# MKR1000.net
KiCad netlist of a schematic drawn in EAGLE
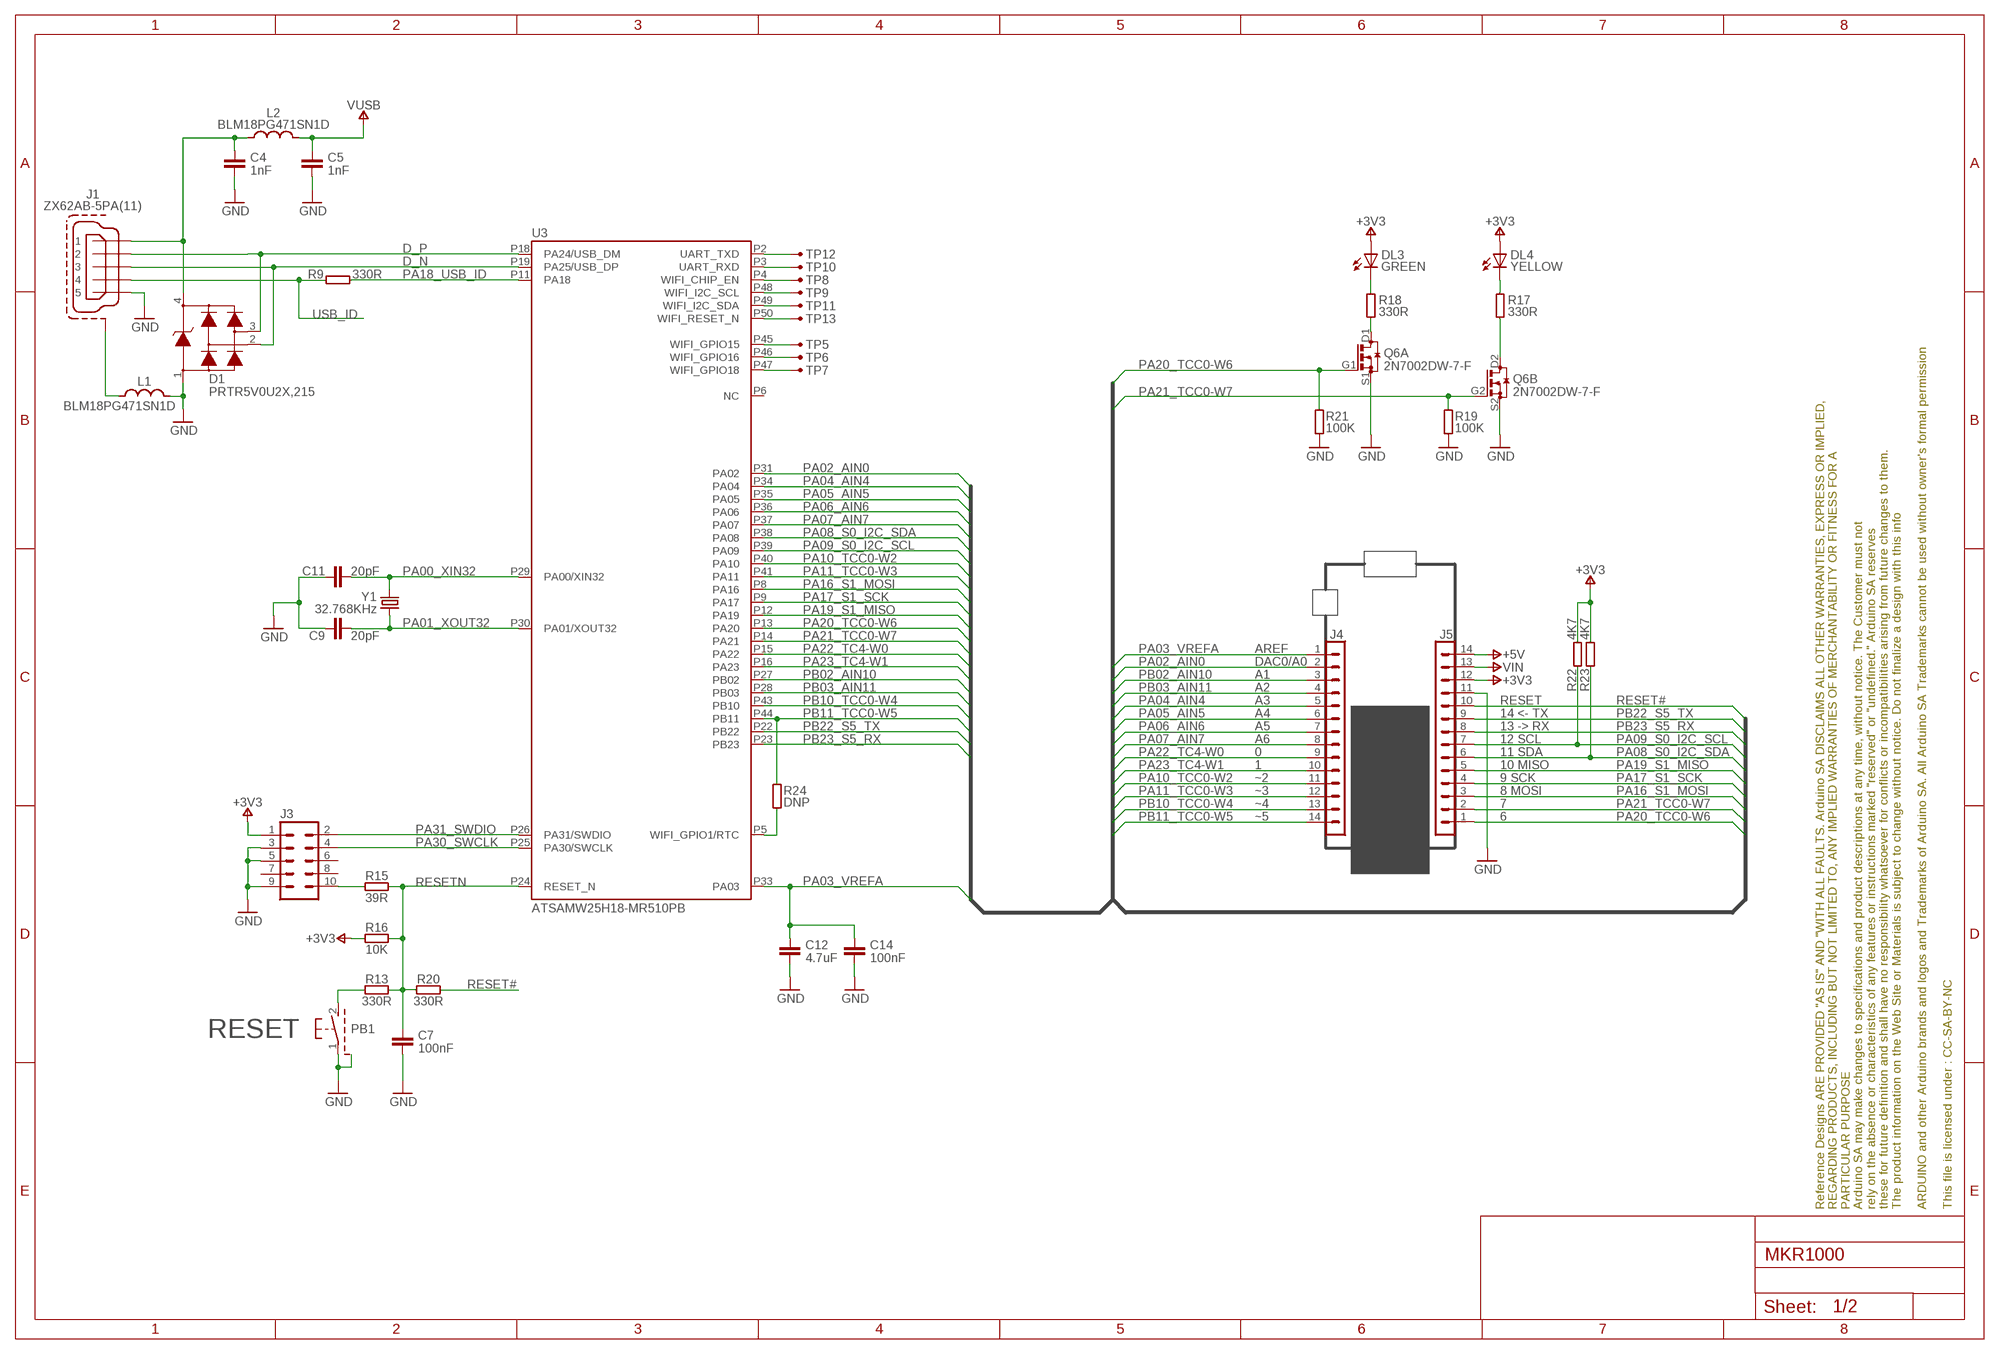
[diagram p0: schematic, sheet 1]
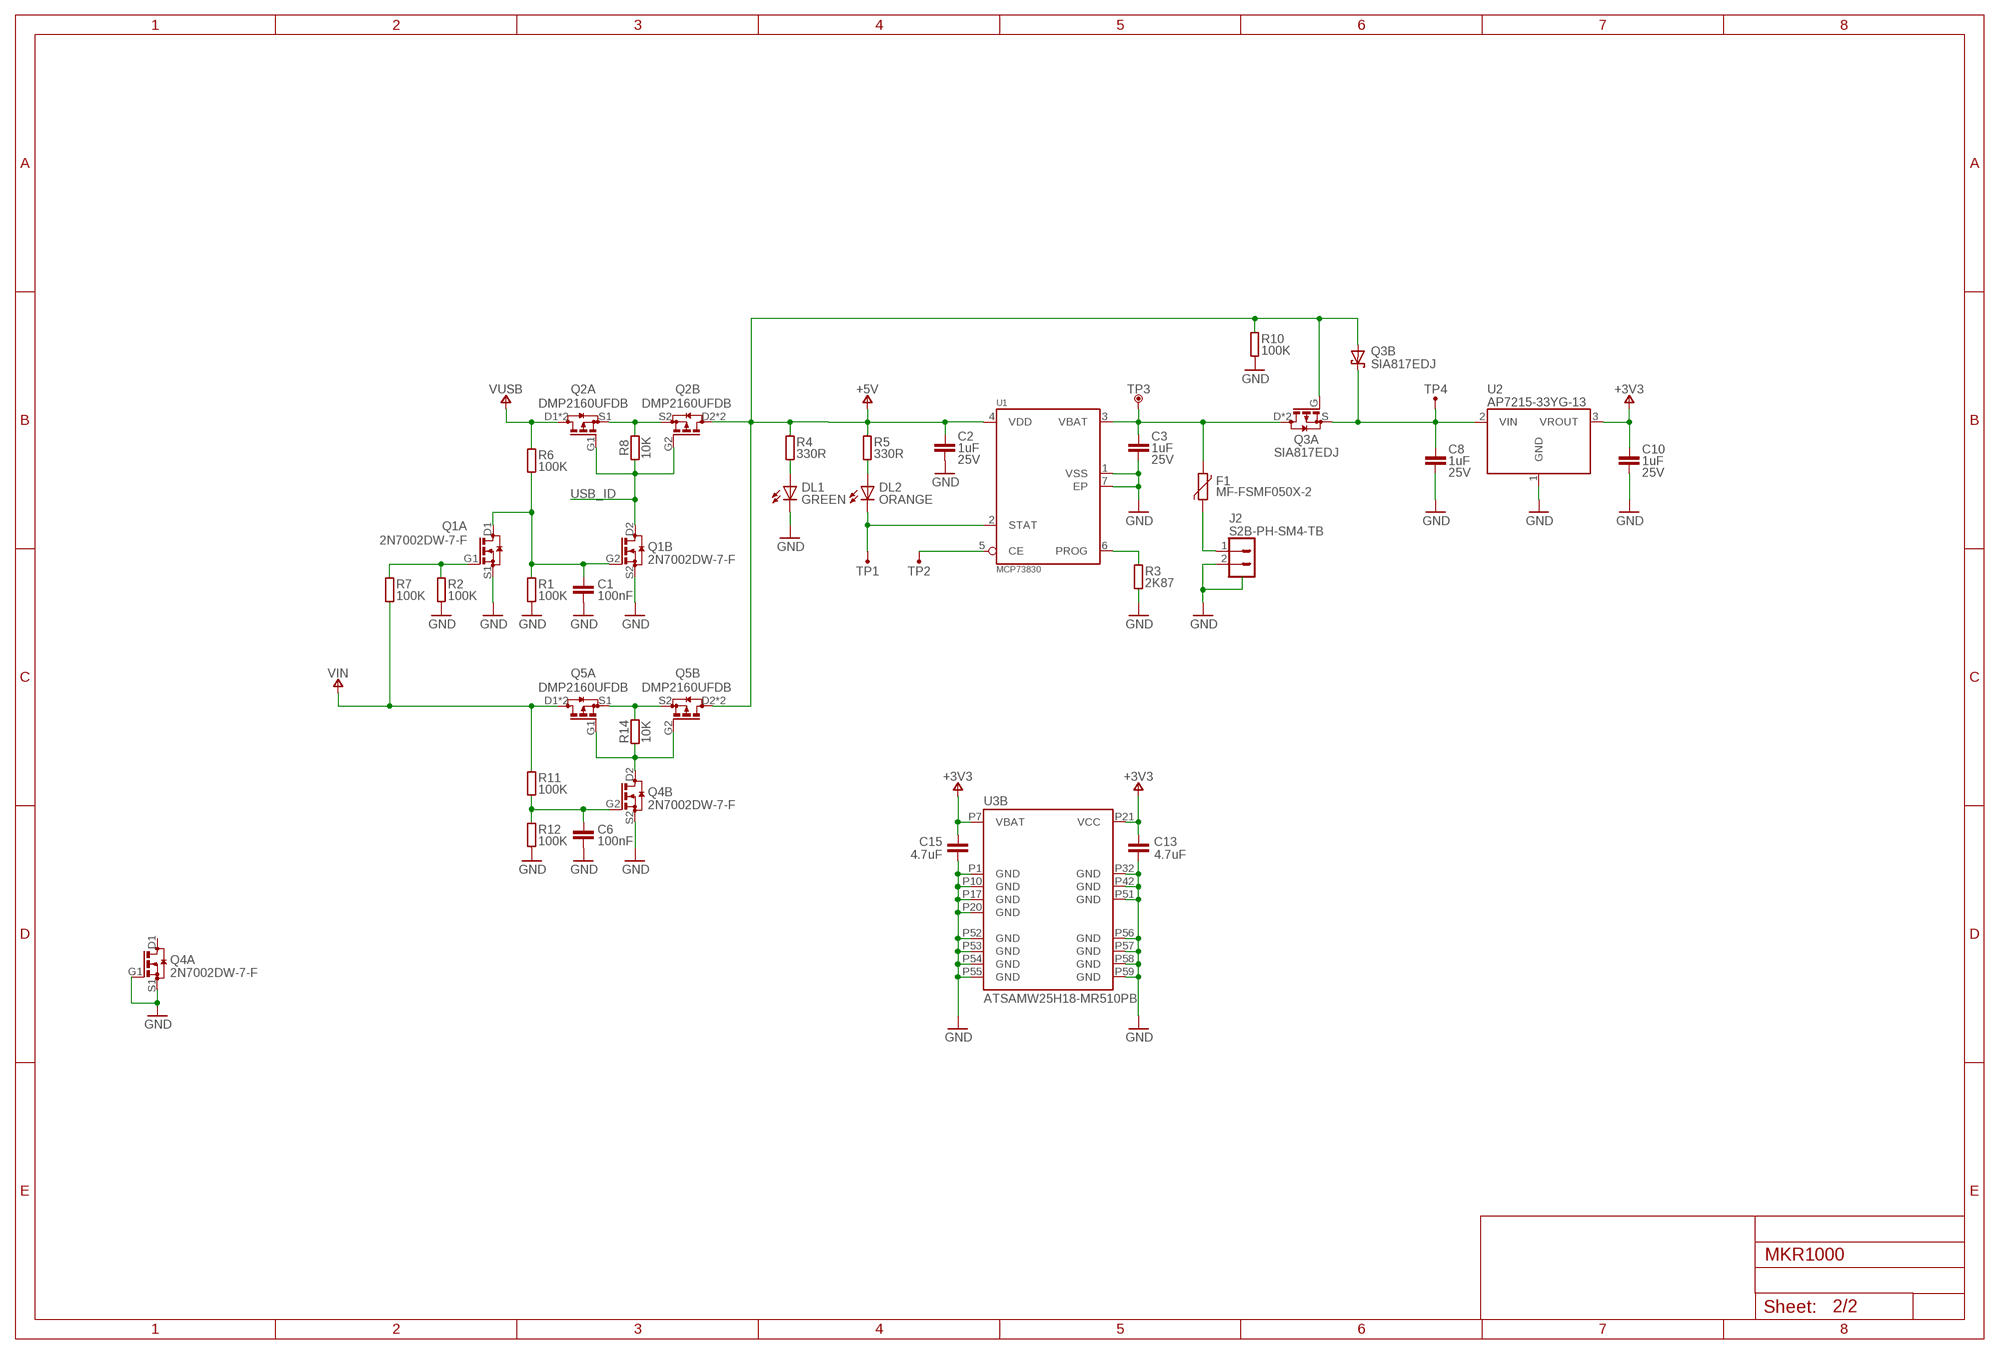
[diagram p1: schematic, sheet 2]

(export (version "E")
  (design (tool "Eeschema 10.0.6"))
  (components
    (comp (ref "C1")
      (value "100nF")
      (footprint "eagle-import:0402-1005X55N")
      (fields (field (name "MF") "TDK") (field (name "MPN") "C1005X5R1H104K050BB "))
      (libsource (lib "eagle-import") (part "C-0402-100NF"))
    )
    (comp (ref "C2")
      (value "1uF")
      (footprint "eagle-import:0402-1005X55N")
      (fields
        (field (name "MF") "Murata")
        (field (name "MPN") "GRM155R61E105KA12D ")
        (field (name "VOLTAGE") "25V")
      )
      (libsource (lib "eagle-import") (part "C-0402-1UF"))
    )
    (comp (ref "C3")
      (value "1uF")
      (footprint "eagle-import:0402-1005X55N")
      (fields
        (field (name "MF") "Murata")
        (field (name "MPN") "GRM155R61E105KA12D ")
        (field (name "VOLTAGE") "25V")
      )
      (libsource (lib "eagle-import") (part "C-0402-1UF"))
    )
    (comp (ref "C6")
      (value "100nF")
      (footprint "eagle-import:0402-1005X55N")
      (fields (field (name "MF") "TDK") (field (name "MPN") "C1005X5R1H104K050BB "))
      (libsource (lib "eagle-import") (part "C-0402-100NF"))
    )
    (comp (ref "C8")
      (value "1uF")
      (footprint "eagle-import:0402-1005X55N")
      (fields
        (field (name "MF") "Murata")
        (field (name "MPN") "GRM155R61E105KA12D ")
        (field (name "VOLTAGE") "25V")
      )
      (libsource (lib "eagle-import") (part "C-0402-1UF"))
    )
    (comp (ref "C10")
      (value "1uF")
      (footprint "eagle-import:0402-1005X55N")
      (fields
        (field (name "MF") "Murata")
        (field (name "MPN") "GRM155R61E105KA12D ")
        (field (name "VOLTAGE") "25V")
      )
      (libsource (lib "eagle-import") (part "C-0402-1UF"))
    )
    (comp (ref "C13")
      (value "4.7uF")
      (footprint "eagle-import:0402-1005X55N")
      (fields (field (name "MF") "Murata") (field (name "MPN") "GRM155R60J475ME47D "))
      (libsource (lib "eagle-import") (part "C-0402-4.7UF"))
    )
    (comp (ref "C15")
      (value "4.7uF")
      (footprint "eagle-import:0402-1005X55N")
      (fields (field (name "MF") "Murata") (field (name "MPN") "GRM155R60J475ME47D "))
      (libsource (lib "eagle-import") (part "C-0402-4.7UF"))
    )
    (comp (ref "DL1")
      (value "GREEN")
      (footprint "eagle-import:LEDC1608X80N-AK")
      (fields (field (name "MF") "Avago ") (field (name "MPN") "HSMG-C190 "))
      (libsource (lib "eagle-import") (part "LED-0603-GREEN"))
    )
    (comp (ref "DL2")
      (value "ORANGE")
      (footprint "eagle-import:LEDC1608X80N-AK")
      (fields (field (name "MF") "Avago ") (field (name "MPN") "HSMD-C190 "))
      (libsource (lib "eagle-import") (part "LED-0603-ORANGE"))
    )
    (comp (ref "F1")
      (value "MF-FSMF050X-2")
      (footprint "eagle-import:0603-F1608X100N")
      (fields (field (name "MF") "Bourns Inc ") (field (name "MPN") "MF-FSMF050X-2 "))
      (libsource (lib "eagle-import") (part "MF-FSMF050X-2"))
    )
    (comp (ref "FRAME2")
      (value "Page 2")
      (footprint "eagle-import:FRAME-NO-BAN-FRAMEONLY")
      (libsource (lib "eagle-import") (part "A3-FRAMEONLY"))
    )
    (comp (ref "J2")
      (value "S2B-PH-SM4-TB")
      (footprint "eagle-import:JST-S2B-PH-SM4-TB")
      (fields (field (name "MF") "JST ") (field (name "MPN") "S2B-PH-SM4-TB(LF)(SN) "))
      (libsource (lib "eagle-import") (part "S2B-PH-SM4-TB"))
    )
    (comp (ref "Q1")
      (value "2N7002DW-7-F")
      (footprint "eagle-import:SOT65P210X110-6AN-DM")
      (fields (field (name "MF") "Diodes Inc ") (field (name "MPN") "2N7002DW-7-F "))
      (libsource (lib "eagle-import") (part "2N7002DW-7-F"))
    )
    (comp (ref "Q2")
      (value "DMP2160UFDB")
      (footprint "eagle-import:SON65P200X200X60-8N-DM")
      (fields (field (name "MF") "Diodes Inc ") (field (name "MPN") "DMP2160UFDB-7 "))
      (libsource (lib "eagle-import") (part "DMP2160UFDB"))
    )
    (comp (ref "Q3")
      (value "SIA817EDJ")
      (footprint "eagle-import:SON65P205X205X75-8N-MWSD")
      (fields (field (name "MF") "Vishay ") (field (name "MPN") "SIA817EDJ-T1-GE3 "))
      (libsource (lib "eagle-import") (part "SIA817EDJ"))
    )
    (comp (ref "Q4")
      (value "2N7002DW-7-F")
      (footprint "eagle-import:SOT65P210X110-6AN-DM")
      (fields (field (name "MF") "Diodes Inc ") (field (name "MPN") "2N7002DW-7-F "))
      (libsource (lib "eagle-import") (part "2N7002DW-7-F"))
    )
    (comp (ref "Q5")
      (value "DMP2160UFDB")
      (footprint "eagle-import:SON65P200X200X60-8N-DM")
      (fields (field (name "MF") "Diodes Inc ") (field (name "MPN") "DMP2160UFDB-7 "))
      (libsource (lib "eagle-import") (part "DMP2160UFDB"))
    )
    (comp (ref "R1")
      (value "100K")
      (footprint "eagle-import:0402-1005X55N")
      (fields (field (name "MF") "Yageo ") (field (name "MPN") "RC0402FR-07100KL "))
      (libsource (lib "eagle-import") (part "R-0402-100K"))
    )
    (comp (ref "R2")
      (value "100K")
      (footprint "eagle-import:0402-1005X55N")
      (fields (field (name "MF") "Yageo ") (field (name "MPN") "RC0402FR-07100KL "))
      (libsource (lib "eagle-import") (part "R-0402-100K"))
    )
    (comp (ref "R3")
      (value "2K87")
      (footprint "eagle-import:0805-R2013X50N")
      (fields (field (name "MF") "Panasonic ") (field (name "MPN") "ERJ6ENF2871V "))
      (libsource (lib "eagle-import") (part "R-0805-2K87"))
    )
    (comp (ref "R4")
      (value "330R")
      (footprint "eagle-import:0402-1005X55N")
      (fields (field (name "MF") "Yageo ") (field (name "MPN") "RC0402FR-07330RL "))
      (libsource (lib "eagle-import") (part "R-0402-330R"))
    )
    (comp (ref "R5")
      (value "330R")
      (footprint "eagle-import:0402-1005X55N")
      (fields (field (name "MF") "Yageo ") (field (name "MPN") "RC0402FR-07330RL "))
      (libsource (lib "eagle-import") (part "R-0402-330R"))
    )
    (comp (ref "R6")
      (value "100K")
      (footprint "eagle-import:0402-1005X55N")
      (fields (field (name "MF") "Yageo ") (field (name "MPN") "RC0402FR-07100KL "))
      (libsource (lib "eagle-import") (part "R-0402-100K"))
    )
    (comp (ref "R7")
      (value "100K")
      (footprint "eagle-import:0402-1005X55N")
      (fields (field (name "MF") "Yageo ") (field (name "MPN") "RC0402FR-07100KL "))
      (libsource (lib "eagle-import") (part "R-0402-100K"))
    )
    (comp (ref "R8")
      (value "10K")
      (footprint "eagle-import:0402-1005X55N")
      (fields (field (name "MF") "Yageo") (field (name "MPN") "RC0402FR-0710KL"))
      (libsource (lib "eagle-import") (part "R-0402-10K"))
    )
    (comp (ref "R10")
      (value "100K")
      (footprint "eagle-import:0402-1005X55N")
      (fields (field (name "MF") "Yageo ") (field (name "MPN") "RC0402FR-07100KL "))
      (libsource (lib "eagle-import") (part "R-0402-100K"))
    )
    (comp (ref "R11")
      (value "100K")
      (footprint "eagle-import:0402-1005X55N")
      (fields (field (name "MF") "Yageo ") (field (name "MPN") "RC0402FR-07100KL "))
      (libsource (lib "eagle-import") (part "R-0402-100K"))
    )
    (comp (ref "R12")
      (value "100K")
      (footprint "eagle-import:0402-1005X55N")
      (fields (field (name "MF") "Yageo ") (field (name "MPN") "RC0402FR-07100KL "))
      (libsource (lib "eagle-import") (part "R-0402-100K"))
    )
    (comp (ref "R14")
      (value "10K")
      (footprint "eagle-import:0402-1005X55N")
      (fields (field (name "MF") "Yageo") (field (name "MPN") "RC0402FR-0710KL"))
      (libsource (lib "eagle-import") (part "R-0402-10K"))
    )
    (comp (ref "TP1")
      (value "TESTPAD")
      (footprint "eagle-import:PAD-SMD")
      (libsource (lib "eagle-import") (part "TESTPAD"))
    )
    (comp (ref "TP2")
      (value "TESTPAD")
      (footprint "eagle-import:PAD-SMD")
      (libsource (lib "eagle-import") (part "TESTPAD"))
    )
    (comp (ref "TP3")
      (value "TESTPOINT")
      (footprint "eagle-import:TESTPOINT-60MLS-F0_9MM")
      (libsource (lib "eagle-import") (part "TESTPOINT"))
    )
    (comp (ref "TP4")
      (value "TESTPAD")
      (footprint "eagle-import:PAD-SMD")
      (libsource (lib "eagle-import") (part "TESTPAD"))
    )
    (comp (ref "U1")
      (value "MCP73830")
      (footprint "eagle-import:SON50P200X200X80-7N-EP160X60")
      (fields (field (name "MF") "Microchip ") (field (name "MPN") "MCP73830T-2AAI/MYY "))
      (libsource (lib "eagle-import") (part "MCP73830"))
    )
    (comp (ref "U2")
      (value "AP7215-33YG-13")
      (footprint "eagle-import:SOT150P400X160-3N")
      (fields (field (name "MF") "Diodes Inc ") (field (name "MPN") "AP7215-33YG-13 "))
      (libsource (lib "eagle-import") (part "AP7215-33YG-13"))
    )
    (comp (ref "U3")
      (value "ATSAMW25H18-MR510PB")
      (footprint "eagle-import:SAMW25")
      (fields (field (name "MF") "Atmel"))
      (libsource (lib "eagle-import") (part "ATSAMW25H18-MR510PB"))
    )
    (comp (ref "C4")
      (value "1nF")
      (footprint "eagle-import:0402-1005X55N")
      (fields (field (name "MF") "Samsung") (field (name "MPN") "CL05B102KB5NNNC "))
      (libsource (lib "eagle-import") (part "C-0402-1NF"))
    )
    (comp (ref "C5")
      (value "1nF")
      (footprint "eagle-import:0402-1005X55N")
      (fields (field (name "MF") "Samsung") (field (name "MPN") "CL05B102KB5NNNC "))
      (libsource (lib "eagle-import") (part "C-0402-1NF"))
    )
    (comp (ref "C7")
      (value "100nF")
      (footprint "eagle-import:0402-1005X55N")
      (fields (field (name "MF") "TDK") (field (name "MPN") "C1005X5R1H104K050BB "))
      (libsource (lib "eagle-import") (part "C-0402-100NF"))
    )
    (comp (ref "C9")
      (value "20pF")
      (footprint "eagle-import:0402-1005X55N")
      (fields (field (name "MF") "Kemet") (field (name "MPN") "CBR04C200J5GAC "))
      (libsource (lib "eagle-import") (part "C-0402-20PF"))
    )
    (comp (ref "C11")
      (value "20pF")
      (footprint "eagle-import:0402-1005X55N")
      (fields (field (name "MF") "Kemet") (field (name "MPN") "CBR04C200J5GAC "))
      (libsource (lib "eagle-import") (part "C-0402-20PF"))
    )
    (comp (ref "C12")
      (value "4.7uF")
      (footprint "eagle-import:0402-1005X55N")
      (fields (field (name "MF") "Murata") (field (name "MPN") "GRM155R60J475ME47D "))
      (libsource (lib "eagle-import") (part "C-0402-4.7UF"))
    )
    (comp (ref "C14")
      (value "100nF")
      (footprint "eagle-import:0402-1005X55N")
      (fields (field (name "MF") "TDK") (field (name "MPN") "C1005X5R1H104K050BB "))
      (libsource (lib "eagle-import") (part "C-0402-100NF"))
    )
    (comp (ref "D1")
      (value "PRTR5V0U2X,215")
      (footprint "eagle-import:SOT190P230X110-4N")
      (fields (field (name "MF") "NXP") (field (name "MPN") "PRTR5V0U2X,215 "))
      (libsource (lib "eagle-import") (part "PRTR5V0U2X,215"))
    )
    (comp (ref "DL3")
      (value "GREEN")
      (footprint "eagle-import:LEDC1608X80N-AK")
      (fields (field (name "MF") "Avago ") (field (name "MPN") "HSMG-C190 "))
      (libsource (lib "eagle-import") (part "LED-0603-GREEN"))
    )
    (comp (ref "DL4")
      (value "YELLOW")
      (footprint "eagle-import:LEDC1608X80N-AK")
      (fields (field (name "MF") "Avago") (field (name "MPN") "HSMY-C190"))
      (libsource (lib "eagle-import") (part "LED-0603-YELLOW"))
    )
    (comp (ref "FRAME1")
      (value "DNP")
      (footprint "eagle-import:FRAME")
      (libsource (lib "eagle-import") (part "A3-FRAME-STANDARD"))
    )
    (comp (ref "J1")
      (value "ZX62AB-5PA(11)")
      (footprint "eagle-import:USBMICRO-ZX62-AB-5PA")
      (libsource (lib "eagle-import") (part "ZX62AB-5PA(11)"))
    )
    (comp (ref "J3")
      (value "M50-3600542")
      (footprint "eagle-import:FCI-MINITEK127HDR-10")
      (fields (field (name "MF") "Harwin") (field (name "MPN") "M50-3600542 "))
      (libsource (lib "eagle-import") (part "M50-3600542"))
    )
    (comp (ref "J4")
      (value "DNP")
      (footprint "eagle-import:STRIP-14-MODULI-A11")
      (libsource (lib "eagle-import") (part "STRIP-14"))
    )
    (comp (ref "J5")
      (value "DNP")
      (footprint "eagle-import:STRIP-14-MODULI-A11")
      (libsource (lib "eagle-import") (part "STRIP-14"))
    )
    (comp (ref "L1")
      (value "BLM18PG471SN1D")
      (footprint "eagle-import:0603-1608X90N")
      (libsource (lib "eagle-import") (part "BLM18PG471SN1D"))
    )
    (comp (ref "L2")
      (value "BLM18PG471SN1D")
      (footprint "eagle-import:0603-1608X90N")
      (libsource (lib "eagle-import") (part "BLM18PG471SN1D"))
    )
    (comp (ref "PB1")
      (value "PTS820-20MM")
      (footprint "eagle-import:PULS-45X29-PST820")
      (fields (field (name "MF") "C&K"))
      (libsource (lib "eagle-import") (part "PTS820-20MM"))
    )
    (comp (ref "Q6")
      (value "2N7002DW-7-F")
      (footprint "eagle-import:SOT65P210X110-6AN-DM")
      (fields (field (name "MF") "Diodes Inc ") (field (name "MPN") "2N7002DW-7-F "))
      (libsource (lib "eagle-import") (part "2N7002DW-7-F"))
    )
    (comp (ref "R9")
      (value "330R")
      (footprint "eagle-import:0402-1005X55N")
      (fields (field (name "MF") "Yageo ") (field (name "MPN") "RC0402FR-07330RL "))
      (libsource (lib "eagle-import") (part "R-0402-330R"))
    )
    (comp (ref "R13")
      (value "330R")
      (footprint "eagle-import:0402-1005X55N")
      (fields (field (name "MF") "Yageo ") (field (name "MPN") "RC0402FR-07330RL "))
      (libsource (lib "eagle-import") (part "R-0402-330R"))
    )
    (comp (ref "R15")
      (value "39R")
      (footprint "eagle-import:0402-1005X55N")
      (fields (field (name "MF") "Yageo ") (field (name "MPN") "RC0402FR-0739RL "))
      (libsource (lib "eagle-import") (part "R-0402-39R"))
    )
    (comp (ref "R16")
      (value "10K")
      (footprint "eagle-import:0402-1005X55N")
      (fields (field (name "MF") "Yageo") (field (name "MPN") "RC0402FR-0710KL"))
      (libsource (lib "eagle-import") (part "R-0402-10K"))
    )
    (comp (ref "R17")
      (value "330R")
      (footprint "eagle-import:0402-1005X55N")
      (fields (field (name "MF") "Yageo ") (field (name "MPN") "RC0402FR-07330RL "))
      (libsource (lib "eagle-import") (part "R-0402-330R"))
    )
    (comp (ref "R18")
      (value "330R")
      (footprint "eagle-import:0402-1005X55N")
      (fields (field (name "MF") "Yageo ") (field (name "MPN") "RC0402FR-07330RL "))
      (libsource (lib "eagle-import") (part "R-0402-330R"))
    )
    (comp (ref "R19")
      (value "100K")
      (footprint "eagle-import:0402-1005X55N")
      (fields (field (name "MF") "Yageo ") (field (name "MPN") "RC0402FR-07100KL "))
      (libsource (lib "eagle-import") (part "R-0402-100K"))
    )
    (comp (ref "R20")
      (value "330R")
      (footprint "eagle-import:0402-1005X55N")
      (fields (field (name "MF") "Yageo ") (field (name "MPN") "RC0402FR-07330RL "))
      (libsource (lib "eagle-import") (part "R-0402-330R"))
    )
    (comp (ref "R21")
      (value "100K")
      (footprint "eagle-import:0402-1005X55N")
      (fields (field (name "MF") "Yageo ") (field (name "MPN") "RC0402FR-07100KL "))
      (libsource (lib "eagle-import") (part "R-0402-100K"))
    )
    (comp (ref "R22")
      (value "4K7")
      (footprint "eagle-import:0402-1005X55N")
      (fields (field (name "MF") "Yageo ") (field (name "MPN") "RC0402FR-074K7L "))
      (libsource (lib "eagle-import") (part "R-0402-4K7"))
    )
    (comp (ref "R23")
      (value "4K7")
      (footprint "eagle-import:0402-1005X55N")
      (fields (field (name "MF") "Yageo ") (field (name "MPN") "RC0402FR-074K7L "))
      (libsource (lib "eagle-import") (part "R-0402-4K7"))
    )
    (comp (ref "R24")
      (value "DNP")
      (footprint "eagle-import:0402-1005X55N")
      (libsource (lib "eagle-import") (part "R-0402-DNP"))
    )
    (comp (ref "TP5")
      (value "TESTPAD")
      (footprint "eagle-import:PAD-SMD")
      (libsource (lib "eagle-import") (part "TESTPAD"))
    )
    (comp (ref "TP6")
      (value "TESTPAD")
      (footprint "eagle-import:PAD-SMD")
      (libsource (lib "eagle-import") (part "TESTPAD"))
    )
    (comp (ref "TP7")
      (value "TESTPAD")
      (footprint "eagle-import:PAD-SMD")
      (libsource (lib "eagle-import") (part "TESTPAD"))
    )
    (comp (ref "TP8")
      (value "TESTPAD")
      (footprint "eagle-import:PAD-SMD")
      (libsource (lib "eagle-import") (part "TESTPAD"))
    )
    (comp (ref "TP9")
      (value "TESTPAD")
      (footprint "eagle-import:PAD-SMD")
      (libsource (lib "eagle-import") (part "TESTPAD"))
    )
    (comp (ref "TP10")
      (value "TESTPAD")
      (footprint "eagle-import:PAD-SMD")
      (libsource (lib "eagle-import") (part "TESTPAD"))
    )
    (comp (ref "TP11")
      (value "TESTPAD")
      (footprint "eagle-import:PAD-SMD")
      (libsource (lib "eagle-import") (part "TESTPAD"))
    )
    (comp (ref "TP12")
      (value "TESTPAD")
      (footprint "eagle-import:PAD-SMD")
      (libsource (lib "eagle-import") (part "TESTPAD"))
    )
    (comp (ref "TP13")
      (value "TESTPAD")
      (footprint "eagle-import:PAD-SMD")
      (libsource (lib "eagle-import") (part "TESTPAD"))
    )
    (comp (ref "Y1")
      (value "32.768KHz")
      (footprint "eagle-import:QUARZO-ABS07")
      (fields (field (name "MF") "Abracon ") (field (name "MPN") "ABS07-32.768KHZ-T "))
      (libsource (lib "eagle-import") (part "ABS07-32.768KHZ-T"))
    )
  )
  (nets
    (net (code "1") (name "+3V3") (class "Default")
      (node (ref "C10") (pin "1") (pinfunction "1_1") (pintype "passive"))
      (node (ref "C13") (pin "1") (pinfunction "1_1") (pintype "passive"))
      (node (ref "C15") (pin "1") (pinfunction "1_1") (pintype "passive"))
      (node (ref "DL3") (pin "A") (pinfunction "A_A") (pintype "passive"))
      (node (ref "DL4") (pin "A") (pinfunction "A_A") (pintype "passive"))
      (node (ref "J3") (pin "1") (pinfunction "1_1") (pintype "passive"))
      (node (ref "J5") (pin "12") (pinfunction "12_12") (pintype "passive"))
      (node (ref "R16") (pin "1") (pinfunction "1_1") (pintype "passive"))
      (node (ref "R22") (pin "2") (pinfunction "2_2") (pintype "passive"))
      (node (ref "R23") (pin "2") (pinfunction "2_2") (pintype "passive"))
      (node (ref "U2") (pin "3") (pinfunction "VROUT_3") (pintype "power_in"))
      (node (ref "U3") (pin "P21") (pinfunction "VCC_P21") (pintype "power_in"))
      (node (ref "U3") (pin "P7") (pinfunction "VBAT_P7") (pintype "power_in"))
    )
    (net (code "2") (name "+5V") (class "Default")
      (node (ref "C2") (pin "1") (pinfunction "1_1") (pintype "passive"))
      (node (ref "J5") (pin "14") (pinfunction "14_14") (pintype "passive"))
      (node (ref "Q2") (pin "D2") (pinfunction "D_D2") (pintype "passive"))
      (node (ref "Q2") (pin "D2'") (pinfunction "D_D2'") (pintype "passive"))
      (node (ref "Q3") (pin "A") (pinfunction "A_A") (pintype "passive"))
      (node (ref "Q3") (pin "G") (pinfunction "G_G") (pintype "passive"))
      (node (ref "Q5") (pin "D2") (pinfunction "D_D2") (pintype "passive"))
      (node (ref "Q5") (pin "D2'") (pinfunction "D_D2'") (pintype "passive"))
      (node (ref "R10") (pin "2") (pinfunction "2_2") (pintype "passive"))
      (node (ref "R4") (pin "2") (pinfunction "2_2") (pintype "passive"))
      (node (ref "R5") (pin "2") (pinfunction "2_2") (pintype "passive"))
      (node (ref "U1") (pin "4") (pinfunction "VDD_4") (pintype "power_in"))
    )
    (net (code "3") (name "D_N") (class "Default")
      (node (ref "D1") (pin "2") (pinfunction "2_2") (pintype "passive"))
      (node (ref "J1") (pin "3") (pinfunction "3_3") (pintype "passive"))
      (node (ref "U3") (pin "P19") (pinfunction "PA25/USB_DP_P19") (pintype "bidirectional"))
    )
    (net (code "4") (name "D_P") (class "Default")
      (node (ref "D1") (pin "3") (pinfunction "3_3") (pintype "passive"))
      (node (ref "J1") (pin "2") (pinfunction "2_2") (pintype "passive"))
      (node (ref "U3") (pin "P18") (pinfunction "PA24/USB_DM_P18") (pintype "bidirectional"))
    )
    (net (code "5") (name "GND") (class "Default")
      (node (ref "C1") (pin "2") (pinfunction "2_2") (pintype "passive"))
      (node (ref "C10") (pin "2") (pinfunction "2_2") (pintype "passive"))
      (node (ref "C11") (pin "1") (pinfunction "1_1") (pintype "passive"))
      (node (ref "C12") (pin "2") (pinfunction "2_2") (pintype "passive"))
      (node (ref "C13") (pin "2") (pinfunction "2_2") (pintype "passive"))
      (node (ref "C14") (pin "2") (pinfunction "2_2") (pintype "passive"))
      (node (ref "C15") (pin "2") (pinfunction "2_2") (pintype "passive"))
      (node (ref "C2") (pin "2") (pinfunction "2_2") (pintype "passive"))
      (node (ref "C3") (pin "2") (pinfunction "2_2") (pintype "passive"))
      (node (ref "C4") (pin "2") (pinfunction "2_2") (pintype "passive"))
      (node (ref "C5") (pin "2") (pinfunction "2_2") (pintype "passive"))
      (node (ref "C6") (pin "2") (pinfunction "2_2") (pintype "passive"))
      (node (ref "C7") (pin "2") (pinfunction "2_2") (pintype "passive"))
      (node (ref "C8") (pin "2") (pinfunction "2_2") (pintype "passive"))
      (node (ref "C9") (pin "1") (pinfunction "1_1") (pintype "passive"))
      (node (ref "D1") (pin "1") (pinfunction "1_1") (pintype "passive"))
      (node (ref "DL1") (pin "C") (pinfunction "C_C") (pintype "passive"))
      (node (ref "J1") (pin "5") (pinfunction "5_5") (pintype "passive"))
      (node (ref "J2") (pin "2") (pinfunction "2_2") (pintype "passive"))
      (node (ref "J2") (pin "3") (pinfunction "SH_3") (pintype "passive"))
      (node (ref "J2") (pin "4") (pinfunction "SH_4") (pintype "passive"))
      (node (ref "J3") (pin "3") (pinfunction "3_3") (pintype "passive"))
      (node (ref "J3") (pin "5") (pinfunction "5_5") (pintype "passive"))
      (node (ref "J3") (pin "9") (pinfunction "9_9") (pintype "passive"))
      (node (ref "J5") (pin "11") (pinfunction "11_11") (pintype "passive"))
      (node (ref "L1") (pin "2") (pinfunction "2_2") (pintype "passive"))
      (node (ref "PB1") (pin "1") (pinfunction "P_1") (pintype "passive"))
      (node (ref "PB1") (pin "3") (pinfunction "SH_3") (pintype "passive"))
      (node (ref "PB1") (pin "4") (pinfunction "SH_4") (pintype "passive"))
      (node (ref "PB1") (pin "5") (pinfunction "SH_5") (pintype "passive"))
      (node (ref "PB1") (pin "6") (pinfunction "SH_6") (pintype "passive"))
      (node (ref "Q1") (pin "S1") (pinfunction "S_S1") (pintype "passive"))
      (node (ref "Q1") (pin "S2") (pinfunction "S_S2") (pintype "passive"))
      (node (ref "Q4") (pin "G1") (pinfunction "G_G1") (pintype "passive"))
      (node (ref "Q4") (pin "S1") (pinfunction "S_S1") (pintype "passive"))
      (node (ref "Q4") (pin "S2") (pinfunction "S_S2") (pintype "passive"))
      (node (ref "Q6") (pin "S1") (pinfunction "S_S1") (pintype "passive"))
      (node (ref "Q6") (pin "S2") (pinfunction "S_S2") (pintype "passive"))
      (node (ref "R1") (pin "1") (pinfunction "1_1") (pintype "passive"))
      (node (ref "R10") (pin "1") (pinfunction "1_1") (pintype "passive"))
      (node (ref "R12") (pin "1") (pinfunction "1_1") (pintype "passive"))
      (node (ref "R19") (pin "1") (pinfunction "1_1") (pintype "passive"))
      (node (ref "R2") (pin "1") (pinfunction "1_1") (pintype "passive"))
      (node (ref "R21") (pin "1") (pinfunction "1_1") (pintype "passive"))
      (node (ref "R3") (pin "1") (pinfunction "1_1") (pintype "passive"))
      (node (ref "U1") (pin "1") (pinfunction "VSS_1") (pintype "power_in"))
      (node (ref "U1") (pin "7") (pinfunction "EP_7") (pintype "passive"))
      (node (ref "U2") (pin "1") (pinfunction "GND_1") (pintype "power_in"))
      (node (ref "U3") (pin "P1") (pinfunction "GND_P1") (pintype "power_in"))
      (node (ref "U3") (pin "P10") (pinfunction "GND_P10") (pintype "power_in"))
      (node (ref "U3") (pin "P17") (pinfunction "GND_P17") (pintype "power_in"))
      (node (ref "U3") (pin "P20") (pinfunction "GND_P20") (pintype "power_in"))
      (node (ref "U3") (pin "P32") (pinfunction "GND_P32") (pintype "power_in"))
      (node (ref "U3") (pin "P42") (pinfunction "GND_P42") (pintype "power_in"))
      (node (ref "U3") (pin "P51") (pinfunction "GND_P51") (pintype "power_in"))
      (node (ref "U3") (pin "P52") (pinfunction "GND_P52") (pintype "power_in"))
      (node (ref "U3") (pin "P53") (pinfunction "GND_P53") (pintype "power_in"))
      (node (ref "U3") (pin "P54") (pinfunction "GND_P54") (pintype "power_in"))
      (node (ref "U3") (pin "P55") (pinfunction "GND_P55") (pintype "power_in"))
      (node (ref "U3") (pin "P56") (pinfunction "GND_P56") (pintype "power_in"))
      (node (ref "U3") (pin "P57") (pinfunction "GND_P57") (pintype "power_in"))
      (node (ref "U3") (pin "P58") (pinfunction "GND_P58") (pintype "power_in"))
      (node (ref "U3") (pin "P59") (pinfunction "GND_P59") (pintype "power_in"))
    )
    (net (code "6") (name "Net-(C4-Pad1)") (class "Default")
      (node (ref "C4") (pin "1") (pinfunction "1_1") (pintype "passive"))
      (node (ref "D1") (pin "4") (pinfunction "4_4") (pintype "passive"))
      (node (ref "J1") (pin "1") (pinfunction "1_1") (pintype "passive"))
      (node (ref "L2") (pin "1") (pinfunction "1_1") (pintype "passive"))
    )
    (net (code "7") (name "Net-(DL1-PadA)") (class "Default")
      (node (ref "DL1") (pin "A") (pinfunction "A_A") (pintype "passive"))
      (node (ref "R4") (pin "1") (pinfunction "1_1") (pintype "passive"))
    )
    (net (code "8") (name "Net-(DL2-PadA)") (class "Default")
      (node (ref "DL2") (pin "A") (pinfunction "A_A") (pintype "passive"))
      (node (ref "R5") (pin "1") (pinfunction "1_1") (pintype "passive"))
    )
    (net (code "9") (name "Net-(DL3-PadC)") (class "Default")
      (node (ref "DL3") (pin "C") (pinfunction "C_C") (pintype "passive"))
      (node (ref "R18") (pin "2") (pinfunction "2_2") (pintype "passive"))
    )
    (net (code "10") (name "Net-(DL4-PadC)") (class "Default")
      (node (ref "DL4") (pin "C") (pinfunction "C_C") (pintype "passive"))
      (node (ref "R17") (pin "2") (pinfunction "2_2") (pintype "passive"))
    )
    (net (code "11") (name "Net-(F1-Pad1)") (class "Default")
      (node (ref "F1") (pin "1") (pinfunction "1_1") (pintype "passive"))
      (node (ref "J2") (pin "1") (pinfunction "1_1") (pintype "passive"))
    )
    (net (code "12") (name "Net-(J1-SH-Pad10)") (class "Default")
      (node (ref "J1") (pin "10") (pinfunction "SH_10") (pintype "passive"))
      (node (ref "J1") (pin "11") (pinfunction "SH_11") (pintype "passive"))
      (node (ref "J1") (pin "6") (pinfunction "SH_6") (pintype "passive"))
      (node (ref "J1") (pin "7") (pinfunction "SH_7") (pintype "passive"))
      (node (ref "J1") (pin "8") (pinfunction "SH_8") (pintype "passive"))
      (node (ref "J1") (pin "9") (pinfunction "SH_9") (pintype "passive"))
      (node (ref "L1") (pin "1") (pinfunction "1_1") (pintype "passive"))
    )
    (net (code "13") (name "Net-(J3-Pad10)") (class "Default")
      (node (ref "J3") (pin "10") (pinfunction "10_10") (pintype "passive"))
      (node (ref "R15") (pin "1") (pinfunction "1_1") (pintype "passive"))
    )
    (net (code "14") (name "Net-(PB1-S)") (class "Default")
      (node (ref "PB1") (pin "2") (pinfunction "S_2") (pintype "passive"))
      (node (ref "R13") (pin "1") (pinfunction "1_1") (pintype "passive"))
    )
    (net (code "15") (name "Net-(Q1A-D)") (class "Default")
      (node (ref "C1") (pin "1") (pinfunction "1_1") (pintype "passive"))
      (node (ref "Q1") (pin "D1") (pinfunction "D_D1") (pintype "passive"))
      (node (ref "Q1") (pin "G2") (pinfunction "G_G2") (pintype "passive"))
      (node (ref "R1") (pin "2") (pinfunction "2_2") (pintype "passive"))
      (node (ref "R6") (pin "1") (pinfunction "1_1") (pintype "passive"))
    )
    (net (code "16") (name "Net-(Q1A-G)") (class "Default")
      (node (ref "Q1") (pin "G1") (pinfunction "G_G1") (pintype "passive"))
      (node (ref "R2") (pin "2") (pinfunction "2_2") (pintype "passive"))
      (node (ref "R7") (pin "2") (pinfunction "2_2") (pintype "passive"))
    )
    (net (code "17") (name "Net-(Q2A-S)") (class "Default")
      (node (ref "Q2") (pin "S1") (pinfunction "S_S1") (pintype "passive"))
      (node (ref "Q2") (pin "S2") (pinfunction "S_S2") (pintype "passive"))
      (node (ref "R8") (pin "2") (pinfunction "2_2") (pintype "passive"))
    )
    (net (code "18") (name "Net-(Q4B-D)") (class "Default")
      (node (ref "Q4") (pin "D2") (pinfunction "D_D2") (pintype "passive"))
      (node (ref "Q5") (pin "G1") (pinfunction "G_G1") (pintype "passive"))
      (node (ref "Q5") (pin "G2") (pinfunction "G_G2") (pintype "passive"))
      (node (ref "R14") (pin "1") (pinfunction "1_1") (pintype "passive"))
    )
    (net (code "19") (name "Net-(Q4B-G)") (class "Default")
      (node (ref "C6") (pin "1") (pinfunction "1_1") (pintype "passive"))
      (node (ref "Q4") (pin "G2") (pinfunction "G_G2") (pintype "passive"))
      (node (ref "R11") (pin "1") (pinfunction "1_1") (pintype "passive"))
      (node (ref "R12") (pin "2") (pinfunction "2_2") (pintype "passive"))
    )
    (net (code "20") (name "Net-(Q5A-S)") (class "Default")
      (node (ref "Q5") (pin "S1") (pinfunction "S_S1") (pintype "passive"))
      (node (ref "Q5") (pin "S2") (pinfunction "S_S2") (pintype "passive"))
      (node (ref "R14") (pin "2") (pinfunction "2_2") (pintype "passive"))
    )
    (net (code "21") (name "Net-(Q6A-D)") (class "Default")
      (node (ref "Q6") (pin "D1") (pinfunction "D_D1") (pintype "passive"))
      (node (ref "R18") (pin "1") (pinfunction "1_1") (pintype "passive"))
    )
    (net (code "22") (name "Net-(Q6B-D)") (class "Default")
      (node (ref "Q6") (pin "D2") (pinfunction "D_D2") (pintype "passive"))
      (node (ref "R17") (pin "1") (pinfunction "1_1") (pintype "passive"))
    )
    (net (code "23") (name "Net-(TP1-P$1)") (class "Default")
      (node (ref "DL2") (pin "C") (pinfunction "C_C") (pintype "passive"))
      (node (ref "TP1") (pin "1") (pinfunction "P$1_1") (pintype "passive"))
      (node (ref "U1") (pin "2") (pinfunction "STAT_2") (pintype "open_collector"))
    )
    (net (code "24") (name "Net-(TP2-P$1)") (class "Default")
      (node (ref "TP2") (pin "1") (pinfunction "P$1_1") (pintype "passive"))
      (node (ref "U1") (pin "5") (pinfunction "CE_5") (pintype "input"))
    )
    (net (code "25") (name "Net-(TP3-P$1)") (class "Default")
      (node (ref "C3") (pin "1") (pinfunction "1_1") (pintype "passive"))
      (node (ref "F1") (pin "2") (pinfunction "2_2") (pintype "passive"))
      (node (ref "Q3") (pin "D") (pinfunction "D_D") (pintype "passive"))
      (node (ref "Q3") (pin "D2") (pinfunction "D_D2") (pintype "passive"))
      (node (ref "TP3") (pin "1") (pinfunction "P$1_1") (pintype "passive"))
      (node (ref "U1") (pin "3") (pinfunction "VBAT_3") (pintype "power_in"))
    )
    (net (code "26") (name "Net-(TP4-P$1)") (class "Default")
      (node (ref "C8") (pin "1") (pinfunction "1_1") (pintype "passive"))
      (node (ref "Q3") (pin "K") (pinfunction "C_K") (pintype "passive"))
      (node (ref "Q3") (pin "K2") (pinfunction "C_K2") (pintype "passive"))
      (node (ref "Q3") (pin "S") (pinfunction "S_S") (pintype "passive"))
      (node (ref "TP4") (pin "1") (pinfunction "P$1_1") (pintype "passive"))
      (node (ref "U2") (pin "2") (pinfunction "VIN_2") (pintype "power_in"))
    )
    (net (code "27") (name "Net-(TP5-P$1)") (class "Default")
      (node (ref "TP5") (pin "1") (pinfunction "P$1_1") (pintype "passive"))
      (node (ref "U3") (pin "P45") (pinfunction "WIFI_GPIO15_P45") (pintype "bidirectional"))
    )
    (net (code "28") (name "Net-(TP6-P$1)") (class "Default")
      (node (ref "TP6") (pin "1") (pinfunction "P$1_1") (pintype "passive"))
      (node (ref "U3") (pin "P46") (pinfunction "WIFI_GPIO16_P46") (pintype "bidirectional"))
    )
    (net (code "29") (name "Net-(TP7-P$1)") (class "Default")
      (node (ref "TP7") (pin "1") (pinfunction "P$1_1") (pintype "passive"))
      (node (ref "U3") (pin "P47") (pinfunction "WIFI_GPIO18_P47") (pintype "bidirectional"))
    )
    (net (code "30") (name "Net-(TP8-P$1)") (class "Default")
      (node (ref "TP8") (pin "1") (pinfunction "P$1_1") (pintype "passive"))
      (node (ref "U3") (pin "P4") (pinfunction "WIFI_CHIP_EN_P4") (pintype "bidirectional"))
    )
    (net (code "31") (name "Net-(TP9-P$1)") (class "Default")
      (node (ref "TP9") (pin "1") (pinfunction "P$1_1") (pintype "passive"))
      (node (ref "U3") (pin "P48") (pinfunction "WIFI_I2C_SCL_P48") (pintype "bidirectional"))
    )
    (net (code "32") (name "Net-(TP10-P$1)") (class "Default")
      (node (ref "TP10") (pin "1") (pinfunction "P$1_1") (pintype "passive"))
      (node (ref "U3") (pin "P3") (pinfunction "UART_RXD_P3") (pintype "bidirectional"))
    )
    (net (code "33") (name "Net-(TP11-P$1)") (class "Default")
      (node (ref "TP11") (pin "1") (pinfunction "P$1_1") (pintype "passive"))
      (node (ref "U3") (pin "P49") (pinfunction "WIFI_I2C_SDA_P49") (pintype "bidirectional"))
    )
    (net (code "34") (name "Net-(TP12-P$1)") (class "Default")
      (node (ref "TP12") (pin "1") (pinfunction "P$1_1") (pintype "passive"))
      (node (ref "U3") (pin "P2") (pinfunction "UART_TXD_P2") (pintype "bidirectional"))
    )
    (net (code "35") (name "Net-(TP13-P$1)") (class "Default")
      (node (ref "TP13") (pin "1") (pinfunction "P$1_1") (pintype "passive"))
      (node (ref "U3") (pin "P50") (pinfunction "WIFI_RESET_N_P50") (pintype "bidirectional"))
    )
    (net (code "36") (name "Net-(U1-PROG)") (class "Default")
      (node (ref "R3") (pin "2") (pinfunction "2_2") (pintype "passive"))
      (node (ref "U1") (pin "6") (pinfunction "PROG_6") (pintype "passive"))
    )
    (net (code "37") (name "Net-(U3A-WIFI_GPIO1{slash}RTC)") (class "Default")
      (node (ref "R24") (pin "1") (pinfunction "1_1") (pintype "passive"))
      (node (ref "U3") (pin "P5") (pinfunction "WIFI_GPIO1/RTC_P5") (pintype "bidirectional"))
    )
    (net (code "38") (name "PA00_XIN32") (class "Default")
      (node (ref "C11") (pin "2") (pinfunction "2_2") (pintype "passive"))
      (node (ref "U3") (pin "P29") (pinfunction "PA00/XIN32_P29") (pintype "bidirectional"))
      (node (ref "Y1") (pin "2") (pinfunction "2_2") (pintype "passive"))
    )
    (net (code "39") (name "PA01_XOUT32") (class "Default")
      (node (ref "C9") (pin "2") (pinfunction "2_2") (pintype "passive"))
      (node (ref "U3") (pin "P30") (pinfunction "PA01/XOUT32_P30") (pintype "bidirectional"))
      (node (ref "Y1") (pin "1") (pinfunction "1_1") (pintype "passive"))
    )
    (net (code "40") (name "PA02_AIN0") (class "Default")
      (node (ref "J4") (pin "2") (pinfunction "2_2") (pintype "passive"))
      (node (ref "U3") (pin "P31") (pinfunction "PA02_P31") (pintype "bidirectional"))
    )
    (net (code "41") (name "PA03_VREFA") (class "Default")
      (node (ref "C12") (pin "1") (pinfunction "1_1") (pintype "passive"))
      (node (ref "C14") (pin "1") (pinfunction "1_1") (pintype "passive"))
      (node (ref "J4") (pin "1") (pinfunction "1_1") (pintype "passive"))
      (node (ref "U3") (pin "P33") (pinfunction "PA03_P33") (pintype "bidirectional"))
    )
    (net (code "42") (name "PA04_AIN4") (class "Default")
      (node (ref "J4") (pin "5") (pinfunction "5_5") (pintype "passive"))
      (node (ref "U3") (pin "P34") (pinfunction "PA04_P34") (pintype "bidirectional"))
    )
    (net (code "43") (name "PA05_AIN5") (class "Default")
      (node (ref "J4") (pin "6") (pinfunction "6_6") (pintype "passive"))
      (node (ref "U3") (pin "P35") (pinfunction "PA05_P35") (pintype "bidirectional"))
    )
    (net (code "44") (name "PA06_AIN6") (class "Default")
      (node (ref "J4") (pin "7") (pinfunction "7_7") (pintype "passive"))
      (node (ref "U3") (pin "P36") (pinfunction "PA06_P36") (pintype "bidirectional"))
    )
    (net (code "45") (name "PA07_AIN7") (class "Default")
      (node (ref "J4") (pin "8") (pinfunction "8_8") (pintype "passive"))
      (node (ref "U3") (pin "P37") (pinfunction "PA07_P37") (pintype "bidirectional"))
    )
    (net (code "46") (name "PA08_S0_I2C_SDA") (class "Default")
      (node (ref "J5") (pin "6") (pinfunction "6_6") (pintype "passive"))
      (node (ref "R23") (pin "1") (pinfunction "1_1") (pintype "passive"))
      (node (ref "U3") (pin "P38") (pinfunction "PA08_P38") (pintype "bidirectional"))
    )
    (net (code "47") (name "PA09_S0_I2C_SCL") (class "Default")
      (node (ref "J5") (pin "7") (pinfunction "7_7") (pintype "passive"))
      (node (ref "R22") (pin "1") (pinfunction "1_1") (pintype "passive"))
      (node (ref "U3") (pin "P39") (pinfunction "PA09_P39") (pintype "bidirectional"))
    )
    (net (code "48") (name "PA10_TCC0-W2") (class "Default")
      (node (ref "J4") (pin "11") (pinfunction "11_11") (pintype "passive"))
      (node (ref "U3") (pin "P40") (pinfunction "PA10_P40") (pintype "bidirectional"))
    )
    (net (code "49") (name "PA11_TCC0-W3") (class "Default")
      (node (ref "J4") (pin "12") (pinfunction "12_12") (pintype "passive"))
      (node (ref "U3") (pin "P41") (pinfunction "PA11_P41") (pintype "bidirectional"))
    )
    (net (code "50") (name "PA16_S1_MOSI") (class "Default")
      (node (ref "J5") (pin "3") (pinfunction "3_3") (pintype "passive"))
      (node (ref "U3") (pin "P8") (pinfunction "PA16_P8") (pintype "bidirectional"))
    )
    (net (code "51") (name "PA17_S1_SCK") (class "Default")
      (node (ref "J5") (pin "4") (pinfunction "4_4") (pintype "passive"))
      (node (ref "U3") (pin "P9") (pinfunction "PA17_P9") (pintype "bidirectional"))
    )
    (net (code "52") (name "PA18_USB_ID") (class "Default")
      (node (ref "R9") (pin "2") (pinfunction "2_2") (pintype "passive"))
      (node (ref "U3") (pin "P11") (pinfunction "PA18_P11") (pintype "bidirectional"))
    )
    (net (code "53") (name "PA19_S1_MISO") (class "Default")
      (node (ref "J5") (pin "5") (pinfunction "5_5") (pintype "passive"))
      (node (ref "U3") (pin "P12") (pinfunction "PA19_P12") (pintype "bidirectional"))
    )
    (net (code "54") (name "PA20_TCC0-W6") (class "Default")
      (node (ref "J5") (pin "1") (pinfunction "1_1") (pintype "passive"))
      (node (ref "Q6") (pin "G1") (pinfunction "G_G1") (pintype "passive"))
      (node (ref "R21") (pin "2") (pinfunction "2_2") (pintype "passive"))
      (node (ref "U3") (pin "P13") (pinfunction "PA20_P13") (pintype "bidirectional"))
    )
    (net (code "55") (name "PA21_TCC0-W7") (class "Default")
      (node (ref "J5") (pin "2") (pinfunction "2_2") (pintype "passive"))
      (node (ref "Q6") (pin "G2") (pinfunction "G_G2") (pintype "passive"))
      (node (ref "R19") (pin "2") (pinfunction "2_2") (pintype "passive"))
      (node (ref "U3") (pin "P14") (pinfunction "PA21_P14") (pintype "bidirectional"))
    )
    (net (code "56") (name "PA22_TC4-W0") (class "Default")
      (node (ref "J4") (pin "9") (pinfunction "9_9") (pintype "passive"))
      (node (ref "U3") (pin "P15") (pinfunction "PA22_P15") (pintype "bidirectional"))
    )
    (net (code "57") (name "PA23_TC4-W1") (class "Default")
      (node (ref "J4") (pin "10") (pinfunction "10_10") (pintype "passive"))
      (node (ref "U3") (pin "P16") (pinfunction "PA23_P16") (pintype "bidirectional"))
    )
    (net (code "58") (name "PA30_SWCLK") (class "Default")
      (node (ref "J3") (pin "4") (pinfunction "4_4") (pintype "passive"))
      (node (ref "U3") (pin "P25") (pinfunction "PA30/SWCLK_P25") (pintype "bidirectional"))
    )
    (net (code "59") (name "PA31_SWDIO") (class "Default")
      (node (ref "J3") (pin "2") (pinfunction "2_2") (pintype "passive"))
      (node (ref "U3") (pin "P26") (pinfunction "PA31/SWDIO_P26") (pintype "bidirectional"))
    )
    (net (code "60") (name "PB02_AIN10") (class "Default")
      (node (ref "J4") (pin "3") (pinfunction "3_3") (pintype "passive"))
      (node (ref "U3") (pin "P27") (pinfunction "PB02_P27") (pintype "bidirectional"))
    )
    (net (code "61") (name "PB03_AIN11") (class "Default")
      (node (ref "J4") (pin "4") (pinfunction "4_4") (pintype "passive"))
      (node (ref "U3") (pin "P28") (pinfunction "PB03_P28") (pintype "bidirectional"))
    )
    (net (code "62") (name "PB10_TCC0-W4") (class "Default")
      (node (ref "J4") (pin "13") (pinfunction "13_13") (pintype "passive"))
      (node (ref "U3") (pin "P43") (pinfunction "PB10_P43") (pintype "bidirectional"))
    )
    (net (code "63") (name "PB11_TCC0-W5") (class "Default")
      (node (ref "J4") (pin "14") (pinfunction "14_14") (pintype "passive"))
      (node (ref "R24") (pin "2") (pinfunction "2_2") (pintype "passive"))
      (node (ref "U3") (pin "P44") (pinfunction "PB11_P44") (pintype "bidirectional"))
    )
    (net (code "64") (name "PB22_S5_TX") (class "Default")
      (node (ref "J5") (pin "9") (pinfunction "9_9") (pintype "passive"))
      (node (ref "U3") (pin "P22") (pinfunction "PB22_P22") (pintype "bidirectional"))
    )
    (net (code "65") (name "PB23_S5_RX") (class "Default")
      (node (ref "J5") (pin "8") (pinfunction "8_8") (pintype "passive"))
      (node (ref "U3") (pin "P23") (pinfunction "PB23_P23") (pintype "bidirectional"))
    )
    (net (code "66") (name "RESET#") (class "Default")
      (node (ref "J5") (pin "10") (pinfunction "10_10") (pintype "passive"))
      (node (ref "R20") (pin "2") (pinfunction "2_2") (pintype "passive"))
    )
    (net (code "67") (name "RESETN") (class "Default")
      (node (ref "C7") (pin "1") (pinfunction "1_1") (pintype "passive"))
      (node (ref "R13") (pin "2") (pinfunction "2_2") (pintype "passive"))
      (node (ref "R15") (pin "2") (pinfunction "2_2") (pintype "passive"))
      (node (ref "R16") (pin "2") (pinfunction "2_2") (pintype "passive"))
      (node (ref "R20") (pin "1") (pinfunction "1_1") (pintype "passive"))
      (node (ref "U3") (pin "P24") (pinfunction "RESET_N_P24") (pintype "bidirectional"))
    )
    (net (code "68") (name "USB_ID") (class "Default")
      (node (ref "J1") (pin "4") (pinfunction "4_4") (pintype "passive"))
      (node (ref "Q1") (pin "D2") (pinfunction "D_D2") (pintype "passive"))
      (node (ref "Q2") (pin "G1") (pinfunction "G_G1") (pintype "passive"))
      (node (ref "Q2") (pin "G2") (pinfunction "G_G2") (pintype "passive"))
      (node (ref "R8") (pin "1") (pinfunction "1_1") (pintype "passive"))
      (node (ref "R9") (pin "1") (pinfunction "1_1") (pintype "passive"))
    )
    (net (code "69") (name "VIN") (class "Default")
      (node (ref "J5") (pin "13") (pinfunction "13_13") (pintype "passive"))
      (node (ref "Q5") (pin "D1") (pinfunction "D_D1") (pintype "passive"))
      (node (ref "Q5") (pin "D1'") (pinfunction "D_D1'") (pintype "passive"))
      (node (ref "R11") (pin "2") (pinfunction "2_2") (pintype "passive"))
      (node (ref "R7") (pin "1") (pinfunction "1_1") (pintype "passive"))
    )
    (net (code "70") (name "VUSB") (class "Default")
      (node (ref "C5") (pin "1") (pinfunction "1_1") (pintype "passive"))
      (node (ref "L2") (pin "2") (pinfunction "2_2") (pintype "passive"))
      (node (ref "Q2") (pin "D1") (pinfunction "D_D1") (pintype "passive"))
      (node (ref "Q2") (pin "D1'") (pinfunction "D_D1'") (pintype "passive"))
      (node (ref "R6") (pin "2") (pinfunction "2_2") (pintype "passive"))
    )
    (net (code "71") (name "unconnected-(J3-Pad6)") (class "Default")
      (node (ref "J3") (pin "6") (pinfunction "6_6") (pintype "passive"))
    )
    (net (code "72") (name "unconnected-(J3-Pad7)") (class "Default")
      (node (ref "J3") (pin "7") (pinfunction "7_7") (pintype "passive"))
    )
    (net (code "73") (name "unconnected-(J3-Pad8)") (class "Default")
      (node (ref "J3") (pin "8") (pinfunction "8_8") (pintype "passive"))
    )
    (net (code "74") (name "unconnected-(Q4A-D-PadD1)") (class "Default")
      (node (ref "Q4") (pin "D1") (pinfunction "D_D1") (pintype "passive"))
    )
    (net (code "75") (name "unconnected-(U3A-NC-PadP6)") (class "Default")
      (node (ref "U3") (pin "P6") (pinfunction "NC_P6") (pintype "bidirectional"))
    )
  )
)
